# P04_ADCIND.net
KiCad netlist of a schematic drawn in Altium Designer
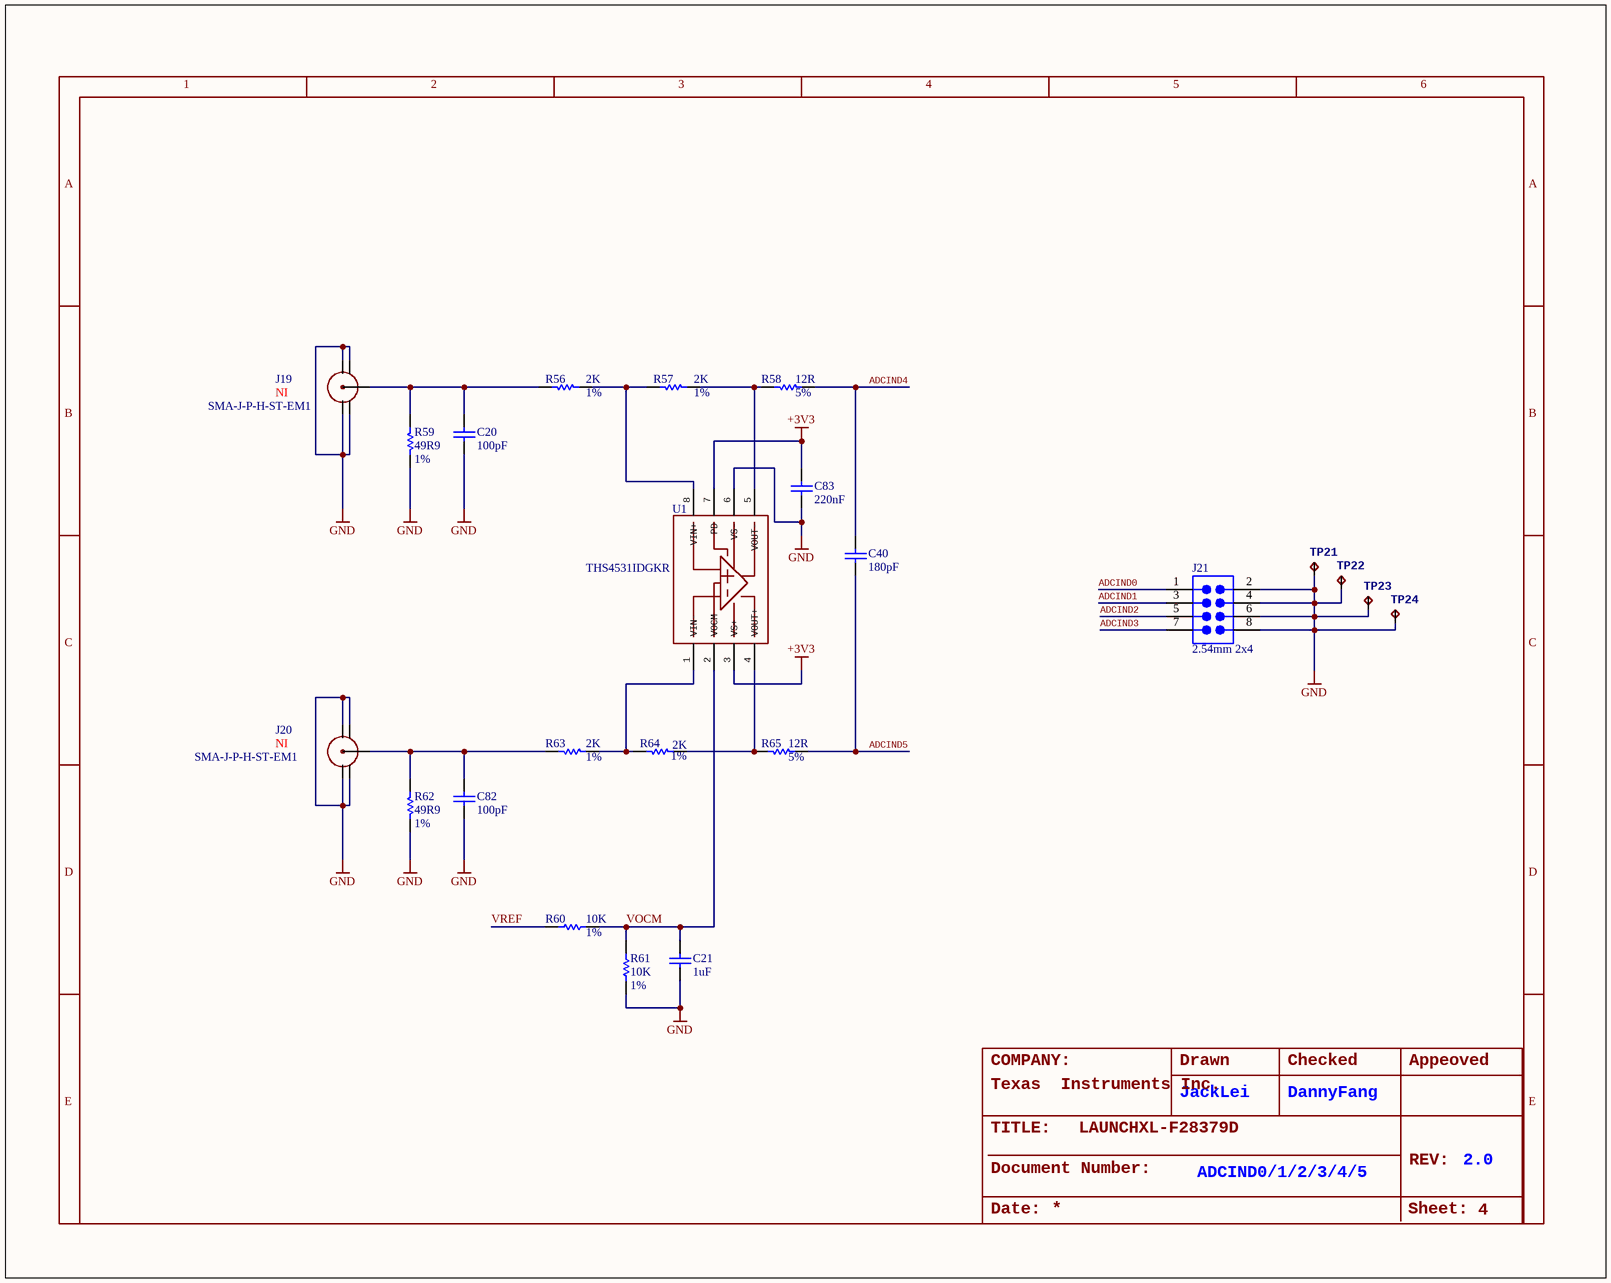
[diagram p0: P04_ADCIND.SchDoc]

(export (version "E")
  (design (tool "Eeschema 10.0.6"))
  (components
    (comp (ref "C20")
      (value "100pF")
      (footprint "C0402")
      (description "CAP,100PF,+/-5%,C0G,50V,SMD0402")
      (fields
        (field (name "MANUFACTURER") "MURATA")
        (field (name "MANUFACTURER PART NUMBER") "GRM1555C1H101JA01D")
      )
      (libsource (lib "Embest") (part "C"))
    )
    (comp (ref "C21")
      (value "1uF")
      (footprint "C0402")
      (description "CAP,1UF,+/-10%,X5R,6.3V,SMD0402")
      (fields
        (field (name "MANUFACTURER") "MURATA")
        (field (name "MANUFACTURER PART NUMBER") "GRM155R60J105KE19D")
      )
      (libsource (lib "Embest") (part "C"))
    )
    (comp (ref "C40")
      (value "180pF")
      (footprint "C0402")
      (description "CAP,180PF,+/-5%,C0G,50V,SMD0402")
      (fields
        (field (name "MANUFACTURER") "MURATA")
        (field (name "MANUFACTURER PART NUMBER") "GRM1555C1H181JA01D")
      )
      (libsource (lib "Embest") (part "C"))
    )
    (comp (ref "C82")
      (value "100pF")
      (footprint "C0402")
      (description "CAP,100PF,+/-5%,C0G,50V,SMD0402")
      (fields
        (field (name "MANUFACTURER") "MURATA")
        (field (name "MANUFACTURER PART NUMBER") "GRM1555C1H101JA01D")
      )
      (libsource (lib "Embest") (part "C"))
    )
    (comp (ref "C83")
      (value "220nF")
      (footprint "C0402")
      (description "CAP,220NF,+/-10%,X5R,10V,SMD0402")
      (fields
        (field (name "MANUFACTURER") "MURATA")
        (field (name "MANUFACTURER PART NUMBER") "GRM155R61A224KE19D")
      )
      (libsource (lib "Embest") (part "C"))
    )
    (comp (ref "J19")
      (value "SMA-J-P-H-ST-EM1")
      (footprint "SMA_EM")
      (description "RF Connector,SMA Jack, Edge Mount, Gold, Straight, 50Ω,SMD,Tray")
      (fields (field (name "ASSY") "NI") (field (name "MANUFACTURER") "SAMTEC"))
      (libsource (lib "Embest") (part "SMA"))
    )
    (comp (ref "J20")
      (value "SMA-J-P-H-ST-EM1")
      (footprint "SMA_EM")
      (description "RF Connector,SMA Jack, Edge Mount, Gold, Straight, 50Ω,SMD,Tray")
      (fields (field (name "ASSY") "NI") (field (name "MANUFACTURER") "SAMTEC"))
      (libsource (lib "Embest") (part "SMA"))
    )
    (comp (ref "J21")
      (value "2.54mm 2x4")
      (footprint "HDRV8W64P254_2X4_1016X500X854P")
      (description "Connector,Pin Header,Straight,Male,2x4Pin,2.54MM pitch,6.06,3.00,Gold Flash 1u, black,DIP")
      (fields
        (field (name "MANUFACTURER") "TOWNES")
        (field (name "MANUFACTURER PART NUMBER") "P101-2*04SGF-116A-NX")
      )
      (libsource (lib "Embest") (part "HEAD2X4"))
    )
    (comp (ref "R56")
      (value "2K")
      (footprint "R0402")
      (description "RES,2K,+/-1%,1/16W,SMD0402")
      (fields
        (field (name "RATING") "1%")
        (field (name "MANUFACTURER") "YAGEO")
        (field (name "MANUFACTURER PART NUMBER") "RC0402FR-072KL")
      )
      (libsource (lib "Embest") (part "R"))
    )
    (comp (ref "R57")
      (value "2K")
      (footprint "R0402")
      (description "RES,2K,+/-1%,1/16W,SMD0402")
      (fields
        (field (name "RATING") "1%")
        (field (name "MANUFACTURER") "YAGEO")
        (field (name "MANUFACTURER PART NUMBER") "RC0402FR-072KL")
      )
      (libsource (lib "Embest") (part "R"))
    )
    (comp (ref "R58")
      (value "12R")
      (footprint "R0402")
      (description "RES SMD 12 OHM 5% 1/16W 0402 TR")
      (fields
        (field (name "RATING") "5%")
        (field (name "MANUFACTURER") "VISHAY")
        (field (name "MANUFACTURER PART NUMBER") "CRCW040212R0JNED")
      )
      (libsource (lib "Embest") (part "R"))
    )
    (comp (ref "R59")
      (value "49R9")
      (footprint "R0402")
      (description "RES,49R9,+/-1%,1/16W,SMD0402")
      (fields
        (field (name "RATING") "1%")
        (field (name "MANUFACTURER") "YAGEO")
        (field (name "MANUFACTURER PART NUMBER") "RC0402FR-0749R9L")
      )
      (libsource (lib "Embest") (part "R"))
    )
    (comp (ref "R60")
      (value "10K")
      (footprint "R0402")
      (description "RES,10K,+/-1%,1/16W,SMD0402")
      (fields
        (field (name "RATING") "1%")
        (field (name "MANUFACTURER") "YAGEO")
        (field (name "MANUFACTURER PART NUMBER") "RC0402FR-0710KL")
      )
      (libsource (lib "Embest") (part "R"))
    )
    (comp (ref "R61")
      (value "10K")
      (footprint "R0402")
      (description "RES,10K,+/-1%,1/16W,SMD0402")
      (fields
        (field (name "RATING") "1%")
        (field (name "MANUFACTURER") "YAGEO")
        (field (name "MANUFACTURER PART NUMBER") "RC0402FR-0710KL")
      )
      (libsource (lib "Embest") (part "R"))
    )
    (comp (ref "R62")
      (value "49R9")
      (footprint "R0402")
      (description "RES,49R9,+/-1%,1/16W,SMD0402")
      (fields
        (field (name "RATING") "1%")
        (field (name "MANUFACTURER") "YAGEO")
        (field (name "MANUFACTURER PART NUMBER") "RC0402FR-0749R9L")
      )
      (libsource (lib "Embest") (part "R"))
    )
    (comp (ref "R63")
      (value "2K")
      (footprint "R0402")
      (description "RES,2K,+/-1%,1/16W,SMD0402")
      (fields
        (field (name "RATING") "1%")
        (field (name "MANUFACTURER") "YAGEO")
        (field (name "MANUFACTURER PART NUMBER") "RC0402FR-072KL")
      )
      (libsource (lib "Embest") (part "R"))
    )
    (comp (ref "R64")
      (value "2K")
      (footprint "R0402")
      (description "RES,2K,+/-1%,1/16W,SMD0402")
      (fields
        (field (name "RATING") "1%")
        (field (name "MANUFACTURER") "YAGEO")
        (field (name "MANUFACTURER PART NUMBER") "RC0402FR-072KL")
      )
      (libsource (lib "Embest") (part "R"))
    )
    (comp (ref "R65")
      (value "12R")
      (footprint "R0402")
      (description "RES SMD 12 OHM 5% 1/16W 0402 TR")
      (fields
        (field (name "RATING") "5%")
        (field (name "MANUFACTURER") "VISHAY")
        (field (name "MANUFACTURER PART NUMBER") "CRCW040212R0JNED")
      )
      (libsource (lib "Embest") (part "R"))
    )
    (comp (ref "TP21")
      (value "TESTPAD_TPB1,27")
      (footprint "TESTPAD_B1,27")
      (description "Test pad")
      (libsource (lib "Embest") (part "TESTPAD_TPB1,27"))
    )
    (comp (ref "TP22")
      (value "TESTPAD_TPB1,27")
      (footprint "TESTPAD_B1,27")
      (description "Test pad")
      (libsource (lib "Embest") (part "TESTPAD_TPB1,27"))
    )
    (comp (ref "TP23")
      (value "TESTPAD_TPB1,27")
      (footprint "TESTPAD_B1,27")
      (description "Test pad")
      (libsource (lib "Embest") (part "TESTPAD_TPB1,27"))
    )
    (comp (ref "TP24")
      (value "TESTPAD_TPB1,27")
      (footprint "TESTPAD_B1,27")
      (description "Test pad")
      (libsource (lib "Embest") (part "TESTPAD_TPB1,27"))
    )
    (comp (ref "U1")
      (value "THS4531IDGKR")
      (footprint "VSSOP65P490X110-8N")
      (description "IC OPAMP DIFF 27MHZ RRO 8VSSOP TR")
      (fields (field (name "MANUFACTURER") "TI"))
      (libsource (lib "Embest") (part "THS4531"))
    )
  )
  (nets
    (net (code "1") (name "+3V3") (class "Default")
      (node (ref "C83") (pin "2") (pinfunction "2_2") (pintype "passive"))
      (node (ref "U1") (pin "3") (pinfunction "VS+_3") (pintype "passive"))
      (node (ref "U1") (pin "7") (pinfunction "PD_7") (pintype "passive"))
    )
    (net (code "2") (name "/ADCIND0") (class "Default")
      (node (ref "J21") (pin "1") (pinfunction "1_1") (pintype "passive"))
    )
    (net (code "3") (name "/ADCIND1") (class "Default")
      (node (ref "J21") (pin "3") (pinfunction "3_3") (pintype "passive"))
    )
    (net (code "4") (name "/ADCIND2") (class "Default")
      (node (ref "J21") (pin "5") (pinfunction "5_5") (pintype "passive"))
    )
    (net (code "5") (name "/ADCIND3") (class "Default")
      (node (ref "J21") (pin "7") (pinfunction "7_7") (pintype "passive"))
    )
    (net (code "6") (name "/ADCIND4") (class "Default")
      (node (ref "C40") (pin "2") (pinfunction "2_2") (pintype "passive"))
      (node (ref "R58") (pin "1") (pinfunction "1_1") (pintype "passive"))
    )
    (net (code "7") (name "/ADCIND5") (class "Default")
      (node (ref "C40") (pin "1") (pinfunction "1_1") (pintype "passive"))
      (node (ref "R65") (pin "1") (pinfunction "1_1") (pintype "passive"))
    )
    (net (code "8") (name "/VOCM") (class "Default")
      (node (ref "C21") (pin "2") (pinfunction "2_2") (pintype "passive"))
      (node (ref "R60") (pin "2") (pinfunction "2_2") (pintype "passive"))
      (node (ref "R61") (pin "1") (pinfunction "1_1") (pintype "passive"))
      (node (ref "U1") (pin "2") (pinfunction "VOCM_2") (pintype "passive"))
    )
    (net (code "9") (name "/VREF") (class "Default")
      (node (ref "R60") (pin "1") (pinfunction "1_1") (pintype "passive"))
    )
    (net (code "10") (name "GND") (class "Default")
      (node (ref "C20") (pin "1") (pinfunction "1_1") (pintype "passive"))
      (node (ref "C21") (pin "1") (pinfunction "1_1") (pintype "passive"))
      (node (ref "C82") (pin "1") (pinfunction "1_1") (pintype "passive"))
      (node (ref "C83") (pin "1") (pinfunction "1_1") (pintype "passive"))
      (node (ref "J19") (pin "1") (pinfunction "1_1") (pintype "passive"))
      (node (ref "J19") (pin "3") (pinfunction "3_3") (pintype "passive"))
      (node (ref "J19") (pin "4") (pinfunction "4_4") (pintype "passive"))
      (node (ref "J19") (pin "5") (pinfunction "5_5") (pintype "passive"))
      (node (ref "J20") (pin "1") (pinfunction "1_1") (pintype "passive"))
      (node (ref "J20") (pin "3") (pinfunction "3_3") (pintype "passive"))
      (node (ref "J20") (pin "4") (pinfunction "4_4") (pintype "passive"))
      (node (ref "J20") (pin "5") (pinfunction "5_5") (pintype "passive"))
      (node (ref "J21") (pin "2") (pinfunction "2_2") (pintype "passive"))
      (node (ref "J21") (pin "4") (pinfunction "4_4") (pintype "passive"))
      (node (ref "J21") (pin "6") (pinfunction "6_6") (pintype "passive"))
      (node (ref "J21") (pin "8") (pinfunction "8_8") (pintype "passive"))
      (node (ref "R59") (pin "1") (pinfunction "1_1") (pintype "passive"))
      (node (ref "R61") (pin "2") (pinfunction "2_2") (pintype "passive"))
      (node (ref "R62") (pin "1") (pinfunction "1_1") (pintype "passive"))
      (node (ref "TP21") (pin "TP") (pinfunction "TP_TP") (pintype "passive"))
      (node (ref "TP22") (pin "TP") (pinfunction "TP_TP") (pintype "passive"))
      (node (ref "TP23") (pin "TP") (pinfunction "TP_TP") (pintype "passive"))
      (node (ref "TP24") (pin "TP") (pinfunction "TP_TP") (pintype "passive"))
      (node (ref "U1") (pin "6") (pinfunction "VS-_6") (pintype "passive"))
    )
    (net (code "11") (name "Net-(C20-Pad2)") (class "Default")
      (node (ref "C20") (pin "2") (pinfunction "2_2") (pintype "passive"))
      (node (ref "J19") (pin "2") (pinfunction "2_2") (pintype "passive"))
      (node (ref "R56") (pin "2") (pinfunction "2_2") (pintype "passive"))
      (node (ref "R59") (pin "2") (pinfunction "2_2") (pintype "passive"))
    )
    (net (code "12") (name "Net-(C82-Pad2)") (class "Default")
      (node (ref "C82") (pin "2") (pinfunction "2_2") (pintype "passive"))
      (node (ref "J20") (pin "2") (pinfunction "2_2") (pintype "passive"))
      (node (ref "R62") (pin "2") (pinfunction "2_2") (pintype "passive"))
      (node (ref "R63") (pin "2") (pinfunction "2_2") (pintype "passive"))
    )
    (net (code "13") (name "Net-(U1-VIN+)") (class "Default")
      (node (ref "R56") (pin "1") (pinfunction "1_1") (pintype "passive"))
      (node (ref "R57") (pin "2") (pinfunction "2_2") (pintype "passive"))
      (node (ref "U1") (pin "8") (pinfunction "VIN+_8") (pintype "passive"))
    )
    (net (code "14") (name "Net-(U1-VIN-)") (class "Default")
      (node (ref "R63") (pin "1") (pinfunction "1_1") (pintype "passive"))
      (node (ref "R64") (pin "2") (pinfunction "2_2") (pintype "passive"))
      (node (ref "U1") (pin "1") (pinfunction "VIN-_1") (pintype "passive"))
    )
    (net (code "15") (name "Net-(U1-VOUT+)") (class "Default")
      (node (ref "R64") (pin "1") (pinfunction "1_1") (pintype "passive"))
      (node (ref "R65") (pin "2") (pinfunction "2_2") (pintype "passive"))
      (node (ref "U1") (pin "4") (pinfunction "VOUT+_4") (pintype "passive"))
    )
    (net (code "16") (name "Net-(U1-VOUT-)") (class "Default")
      (node (ref "R57") (pin "1") (pinfunction "1_1") (pintype "passive"))
      (node (ref "R58") (pin "2") (pinfunction "2_2") (pintype "passive"))
      (node (ref "U1") (pin "5") (pinfunction "VOUT-_5") (pintype "passive"))
    )
  )
)
